# DressingEth.net
KiCad netlist of a schematic drawn in EasyEDA Pro
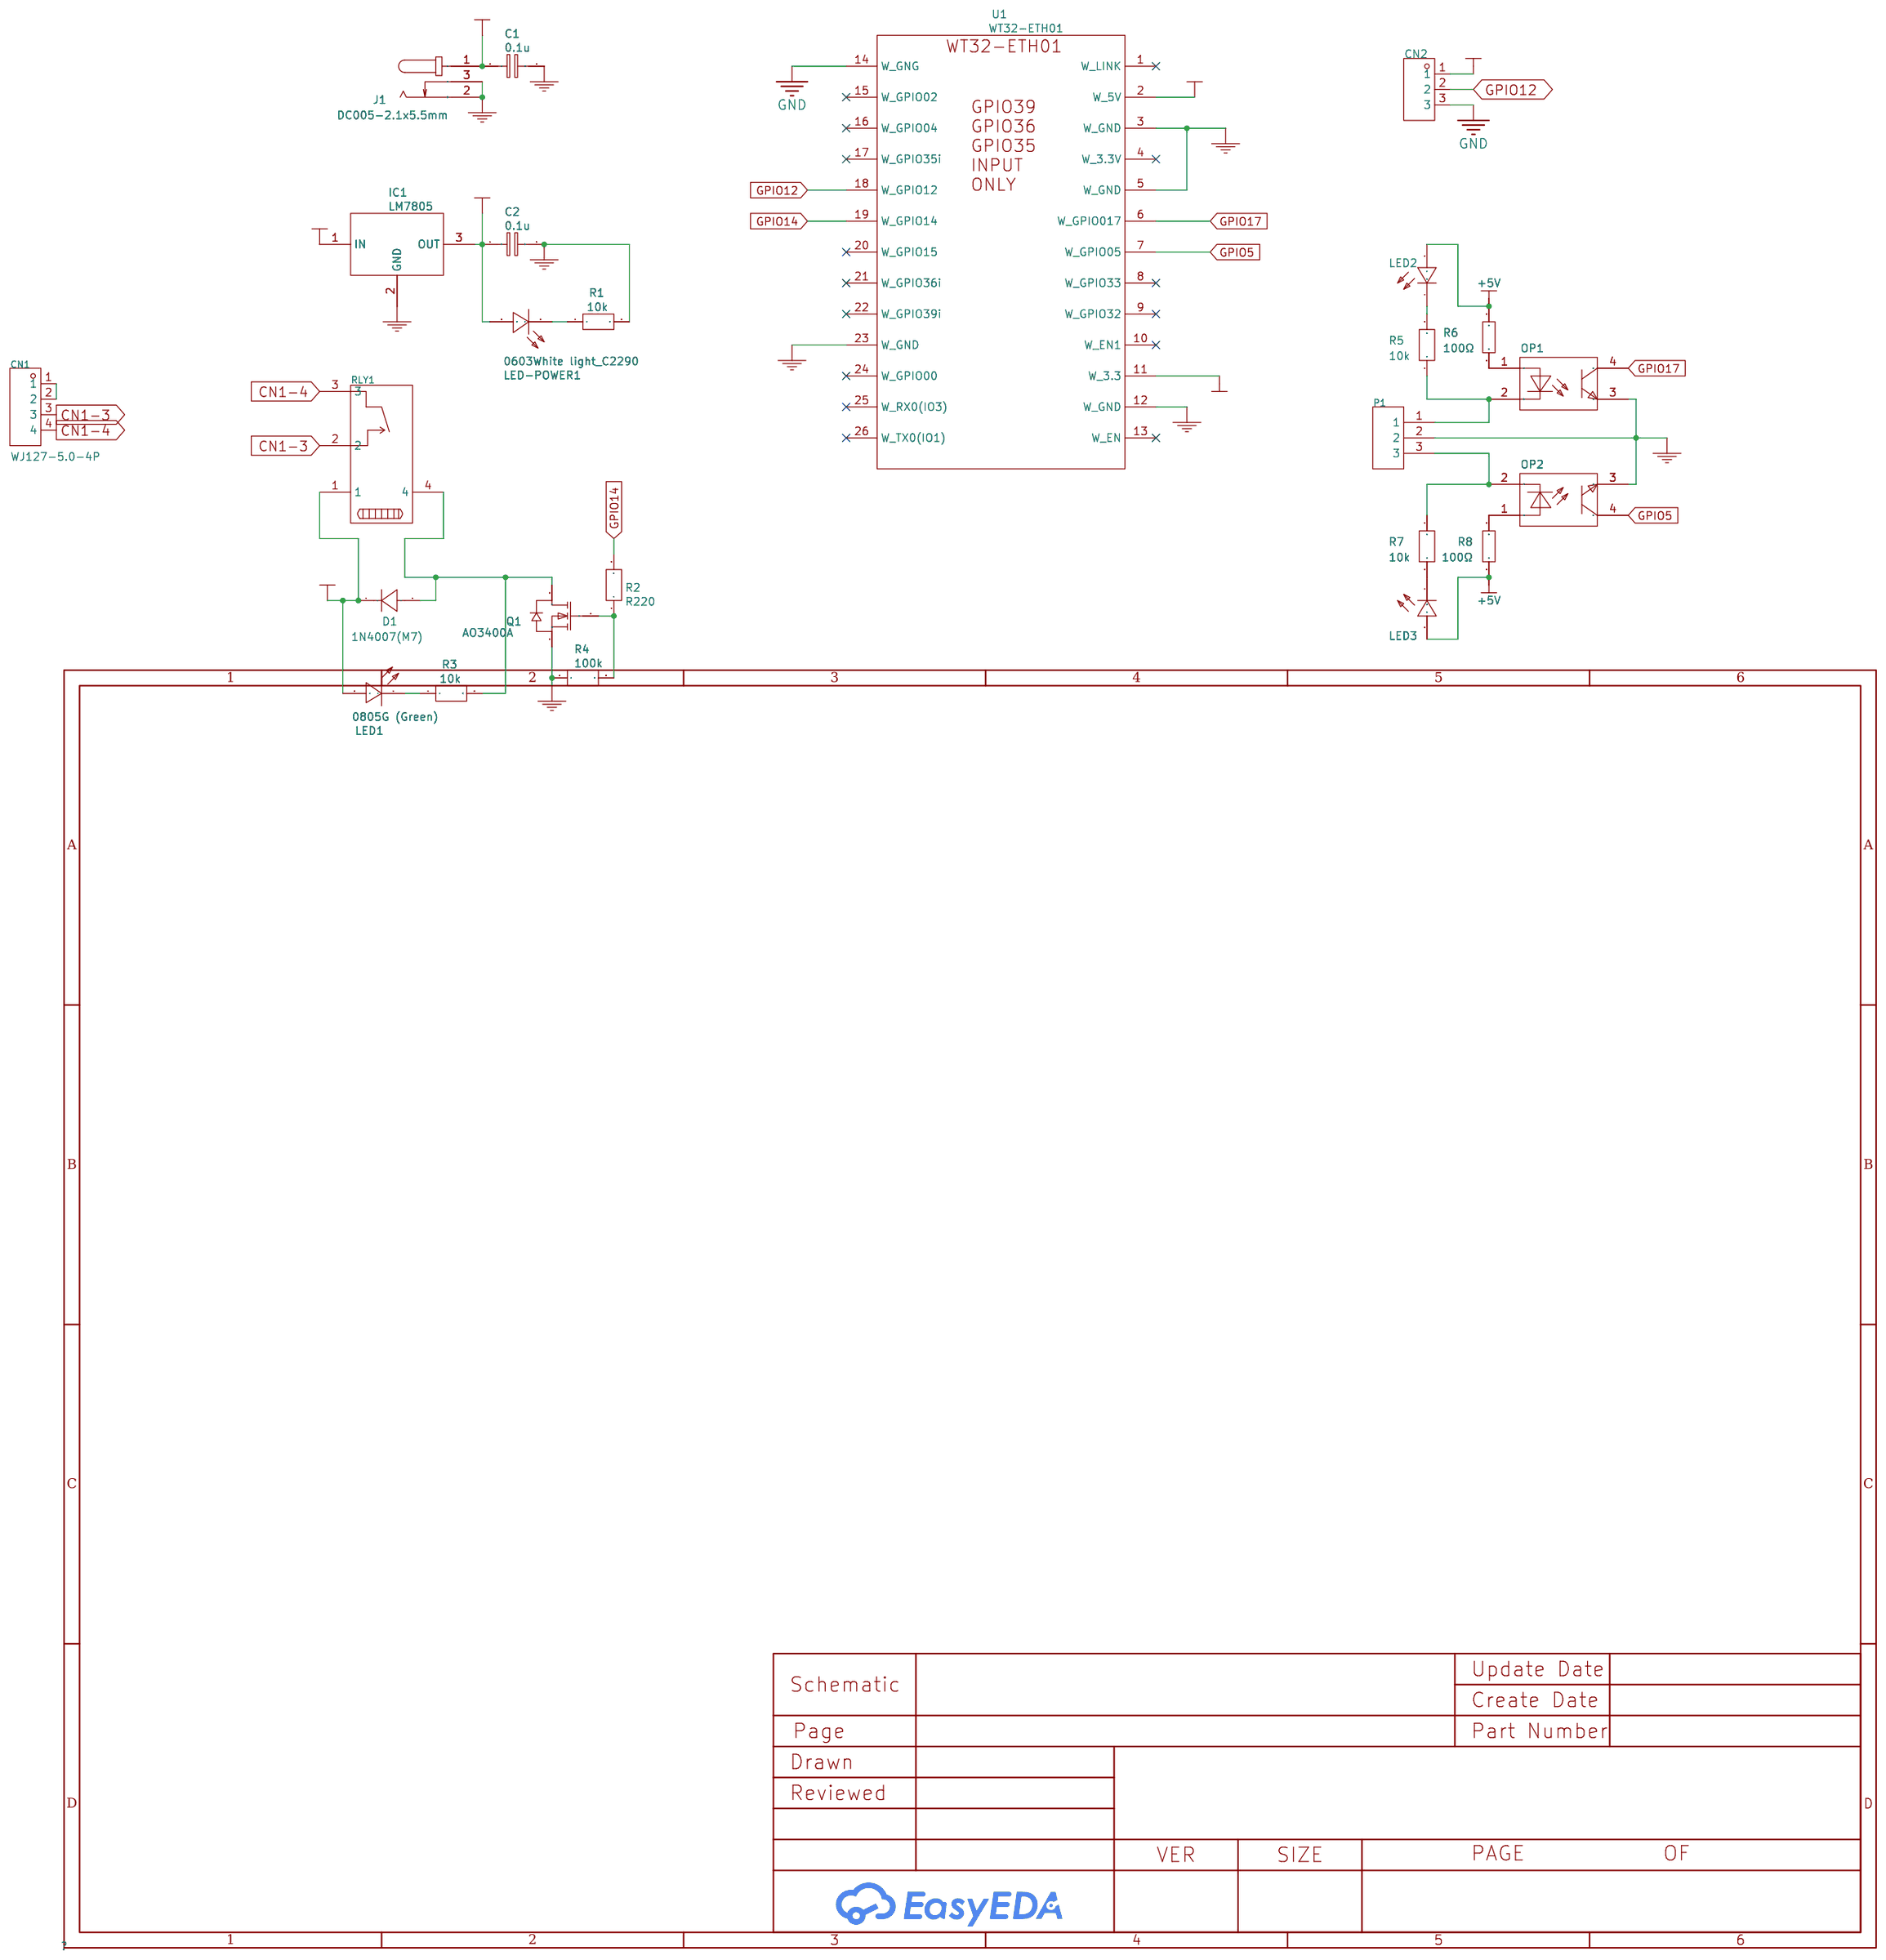
[diagram p0: schematic sheet]

(export (version "E")
  (design (tool "Eeschema 10.0.6"))
  (components
    (comp (ref "C1")
      (value "0.1u")
      (footprint "easyedapro:C0603")
      (fields
        (field (name "Manufacturer Part") "CL05B104KO5NNNC")
        (field (name "Manufacturer") "SAMSUNG(三星)")
      )
      (libsource (lib "easyedapro") (part "0.1u"))
    )
    (comp (ref "C2")
      (value "0.1u")
      (footprint "easyedapro:C0603")
      (fields
        (field (name "Manufacturer Part") "CL05B104KO5NNNC")
        (field (name "Manufacturer") "SAMSUNG(三星)")
      )
      (libsource (lib "easyedapro") (part "0.1u"))
    )
    (comp (ref "CN1")
      (value "WJ127-5.0-4P")
      (footprint "easyedapro:CONN-TH_4P-P5.00_WJ127-5.0-4P")
      (fields (field (name "Manufacturer") "KANGNEX(康奈克斯电气)"))
      (libsource (lib "easyedapro") (part "WJ127-5.0-4P"))
    )
    (comp (ref "CN2")
      (value "XH2.54-3A")
      (footprint "easyedapro:CONN-TH_3P-P2.50_HCTL_XH-3A-L")
      (libsource (lib "easyedapro") (part "XH2.54-3A"))
    )
    (comp (ref "D1")
      (value "1N4007(M7)")
      (footprint "easyedapro:SMA_L4.3-W2.7-LS5.1-RD")
      (fields (field (name "Manufacturer") "UMW(友台半导体)"))
      (libsource (lib "easyedapro") (part "1N4007(M7)"))
    )
    (comp (ref "IC1")
      (value "LM7805")
      (footprint "easyedapro:LM7805")
      (libsource (lib "easyedapro") (part "LM7805"))
    )
    (comp (ref "J1")
      (value "DC005-2.1x5.5mm")
      (footprint "easyedapro:DC-IN-TH_POWER-JACK")
      (fields (field (name "Manufacturer Part") "POWER-JACK") (field (name "Manufacturer") "索峰"))
      (libsource (lib "easyedapro") (part "DC005-2.1x5.5mm"))
    )
    (comp (ref "LED-POWER1")
      (value "0603White light_C2290")
      (footprint "easyedapro:LED0603-R-RD_WHITE")
      (fields (field (name "Manufacturer Part") "KT-0603W") (field (name "Manufacturer") "KENTO"))
      (libsource (lib "easyedapro") (part "0603White light_C2290"))
    )
    (comp (ref "LED1")
      (value "0805G (Green)")
      (footprint "easyedapro:LED0805-RD_GREEN")
      (fields (field (name "Manufacturer") "KENTO"))
      (libsource (lib "easyedapro") (part "0805G (Green)"))
    )
    (comp (ref "LED2")
      (value "19-213/Y2C-CQ2R2L/3T(CY)")
      (footprint "easyedapro:LED0603-RD-YELLOW")
      (fields (field (name "Manufacturer") "EVERLIGHT(亿光)"))
      (libsource (lib "easyedapro") (part "19-213/Y2C-CQ2R2L/3T(CY)"))
    )
    (comp (ref "LED3")
      (value "19-213/Y2C-CQ2R2L/3T(CY)")
      (footprint "easyedapro:LED0603-RD-YELLOW")
      (fields (field (name "Manufacturer") "EVERLIGHT(亿光)"))
      (libsource (lib "easyedapro") (part "19-213/Y2C-CQ2R2L/3T(CY)"))
    )
    (comp (ref "OP1")
      (value "EL817S1(C)(TU)-F")
      (footprint "easyedapro:OPTO-SMD-4_L4.6-W6.5-P2.54-LS10.3-TL")
      (fields (field (name "Manufacturer") "EVERLIGHT(亿光)"))
      (libsource (lib "easyedapro") (part "EL817S1(C)(TU)-F"))
    )
    (comp (ref "OP2")
      (value "EL817S1(C)(TU)-F")
      (footprint "easyedapro:OPTO-SMD-4_L4.6-W6.5-P2.54-LS10.3-TL")
      (fields (field (name "Manufacturer") "EVERLIGHT(亿光)"))
      (libsource (lib "easyedapro") (part "EL817S1(C)(TU)-F"))
    )
    (comp (ref "P1")
      (value "WJ127-5.0-3P")
      (footprint "easyedapro:CONN-TH_3P-P5.00_WJ127-5.0-3P")
      (fields (field (name "Manufacturer") "KANGNEX(康奈克斯电气)"))
      (libsource (lib "easyedapro") (part "WJ127-5.0-3P"))
    )
    (comp (ref "Q1")
      (value "AO3400A")
      (footprint "easyedapro:SOT-23-3_L2.9-W1.6-P1.90-LS2.8-BR")
      (fields (field (name "Manufacturer") "AOS"))
      (libsource (lib "easyedapro") (part "AO3400A"))
    )
    (comp (ref "R1")
      (value "10k")
      (footprint "easyedapro:R0603")
      (fields
        (field (name "Manufacturer Part") "0603WAF1002T5E")
        (field (name "Manufacturer") "UNI-ROYAL(厚声)")
      )
      (libsource (lib "easyedapro") (part "10k"))
    )
    (comp (ref "R2")
      (value "R220")
      (footprint "easyedapro:R0603")
      (fields
        (field (name "Manufacturer Part") "0603WAF2200T5E")
        (field (name "Manufacturer") "UNI-ROYAL(厚声)")
      )
      (libsource (lib "easyedapro") (part "R220"))
    )
    (comp (ref "R3")
      (value "10k")
      (footprint "easyedapro:R0603")
      (fields
        (field (name "Manufacturer Part") "0603WAF1002T5E")
        (field (name "Manufacturer") "UNI-ROYAL(厚声)")
      )
      (libsource (lib "easyedapro") (part "10k"))
    )
    (comp (ref "R4")
      (value "100k")
      (footprint "easyedapro:R0603")
      (fields
        (field (name "Manufacturer Part") "0603WAF1003T5E")
        (field (name "Manufacturer") "UNI-ROYAL(厚声)")
      )
      (libsource (lib "easyedapro") (part "100k"))
    )
    (comp (ref "R5")
      (value "10k")
      (footprint "easyedapro:R0603")
      (fields
        (field (name "Manufacturer Part") "0603WAF1002T5E")
        (field (name "Manufacturer") "UNI-ROYAL(厚声)")
      )
      (libsource (lib "easyedapro") (part "10k"))
    )
    (comp (ref "R6")
      (value "100Ω")
      (footprint "easyedapro:R0805")
      (fields
        (field (name "Manufacturer Part") "0805W8F1000T5E")
        (field (name "Manufacturer") "UNI-ROYAL(厚声)")
      )
      (libsource (lib "easyedapro") (part "0805W8F1000T5E"))
    )
    (comp (ref "R7")
      (value "10k")
      (footprint "easyedapro:R0603")
      (fields
        (field (name "Manufacturer Part") "0603WAF1002T5E")
        (field (name "Manufacturer") "UNI-ROYAL(厚声)")
      )
      (libsource (lib "easyedapro") (part "10k"))
    )
    (comp (ref "R8")
      (value "100Ω")
      (footprint "easyedapro:R0805")
      (fields
        (field (name "Manufacturer Part") "0805W8F1000T5E")
        (field (name "Manufacturer") "UNI-ROYAL(厚声)")
      )
      (libsource (lib "easyedapro") (part "0805W8F1000T5E"))
    )
    (comp (ref "RLY1")
      (value "G5NB-1A-E-DC5V")
      (footprint "easyedapro:RELAY-TH_G5NB-1A-E-DCXX")
      (fields (field (name "Manufacturer") "OMRON(欧姆龙)"))
      (libsource (lib "easyedapro") (part "G5NB-1A-E-DC5V"))
    )
    (comp (ref "U1")
      (value "WT32-ETH01")
      (footprint "easyedapro:WT32-ETH01-M")
      (fields (field (name "Manufacturer") "Wireless-Tag"))
      (libsource (lib "easyedapro") (part "WT32-ETH01"))
    )
  )
  (nets
    (net (code "1") (name "+3.3V") (class "Default")
      (node (ref "CN2") (pin "1") (pinfunction "1_1") (pintype "unspecified"))
      (node (ref "U1") (pin "11") (pinfunction "W_3.3_11") (pintype "unspecified"))
    )
    (net (code "2") (name "+5V") (class "Default")
      (node (ref "C2") (pin "1") (pinfunction "1_1") (pintype "unspecified"))
      (node (ref "D1") (pin "1") (pinfunction "K_1") (pintype "unspecified"))
      (node (ref "IC1") (pin "3") (pinfunction "OUT_3") (pintype "unspecified"))
      (node (ref "LED-POWER1") (pin "1") (pinfunction "A_1") (pintype "unspecified"))
      (node (ref "LED1") (pin "2") (pinfunction "A_2") (pintype "unspecified"))
      (node (ref "LED2") (pin "2") (pinfunction "A_2") (pintype "input"))
      (node (ref "LED3") (pin "2") (pinfunction "A_2") (pintype "input"))
      (node (ref "R6") (pin "1") (pinfunction "1_1") (pintype "input"))
      (node (ref "R8") (pin "1") (pinfunction "1_1") (pintype "input"))
      (node (ref "RLY1") (pin "1") (pinfunction "1_1") (pintype "input"))
      (node (ref "U1") (pin "2") (pinfunction "W_5V_2") (pintype "unspecified"))
    )
    (net (code "3") (name "CN1-3") (class "Default")
      (node (ref "CN1") (pin "3") (pinfunction "3_3") (pintype "input"))
      (node (ref "RLY1") (pin "2") (pinfunction "2_2") (pintype "input"))
    )
    (net (code "4") (name "CN1-4") (class "Default")
      (node (ref "CN1") (pin "4") (pinfunction "4_4") (pintype "input"))
      (node (ref "RLY1") (pin "3") (pinfunction "3_3") (pintype "input"))
    )
    (net (code "5") (name "GND") (class "Default")
      (node (ref "C1") (pin "2") (pinfunction "2_2") (pintype "unspecified"))
      (node (ref "C2") (pin "2") (pinfunction "2_2") (pintype "unspecified"))
      (node (ref "CN2") (pin "3") (pinfunction "3_3") (pintype "unspecified"))
      (node (ref "IC1") (pin "2") (pinfunction "GND_2") (pintype "unspecified"))
      (node (ref "J1") (pin "2") (pinfunction "GND_2") (pintype "unspecified"))
      (node (ref "J1") (pin "3") (pinfunction "3_3") (pintype "unspecified"))
      (node (ref "OP1") (pin "3") (pinfunction "EM_3") (pintype "unspecified"))
      (node (ref "OP2") (pin "3") (pinfunction "EM_3") (pintype "unspecified"))
      (node (ref "P1") (pin "2") (pinfunction "2_2") (pintype "input"))
      (node (ref "Q1") (pin "2") (pinfunction "S_2") (pintype "unspecified"))
      (node (ref "R1") (pin "2") (pinfunction "2_2") (pintype "unspecified"))
      (node (ref "R4") (pin "1") (pinfunction "1_1") (pintype "unspecified"))
      (node (ref "U1") (pin "12") (pinfunction "W_GND_12") (pintype "unspecified"))
      (node (ref "U1") (pin "14") (pinfunction "W_GNG_14") (pintype "unspecified"))
      (node (ref "U1") (pin "23") (pinfunction "W_GND_23") (pintype "unspecified"))
      (node (ref "U1") (pin "3") (pinfunction "W_GND_3") (pintype "unspecified"))
      (node (ref "U1") (pin "5") (pinfunction "W_GND_5") (pintype "unspecified"))
    )
    (net (code "6") (name "GPIO5") (class "Default")
      (node (ref "OP2") (pin "4") (pinfunction "COL_4") (pintype "unspecified"))
      (node (ref "U1") (pin "7") (pinfunction "W_GPIO05_7") (pintype "unspecified"))
    )
    (net (code "7") (name "GPIO12") (class "Default")
      (node (ref "CN2") (pin "2") (pinfunction "2_2") (pintype "unspecified"))
      (node (ref "U1") (pin "18") (pinfunction "W_GPIO12_18") (pintype "unspecified"))
    )
    (net (code "8") (name "GPIO14") (class "Default")
      (node (ref "R2") (pin "2") (pinfunction "2_2") (pintype "unspecified"))
      (node (ref "U1") (pin "19") (pinfunction "W_GPIO14_19") (pintype "unspecified"))
    )
    (net (code "9") (name "GPIO17") (class "Default")
      (node (ref "OP1") (pin "4") (pinfunction "COL_4") (pintype "unspecified"))
      (node (ref "U1") (pin "6") (pinfunction "W_GPIO017_6") (pintype "unspecified"))
    )
    (net (code "10") (name "Net-(CN1-Pad1)") (class "Default")
      (node (ref "CN1") (pin "1") (pinfunction "1_1") (pintype "input"))
      (node (ref "CN1") (pin "2") (pinfunction "2_2") (pintype "input"))
    )
    (net (code "11") (name "Net-(D1-A)") (class "Default")
      (node (ref "D1") (pin "2") (pinfunction "A_2") (pintype "unspecified"))
      (node (ref "Q1") (pin "3") (pinfunction "D_3") (pintype "unspecified"))
      (node (ref "R3") (pin "2") (pinfunction "2_2") (pintype "unspecified"))
      (node (ref "RLY1") (pin "4") (pinfunction "4_4") (pintype "input"))
    )
    (net (code "12") (name "Net-(LED-POWER1-K)") (class "Default")
      (node (ref "LED-POWER1") (pin "2") (pinfunction "K_2") (pintype "unspecified"))
      (node (ref "R1") (pin "1") (pinfunction "1_1") (pintype "unspecified"))
    )
    (net (code "13") (name "Net-(LED1-K)") (class "Default")
      (node (ref "LED1") (pin "1") (pinfunction "K_1") (pintype "unspecified"))
      (node (ref "R3") (pin "1") (pinfunction "1_1") (pintype "unspecified"))
    )
    (net (code "14") (name "Net-(LED2-C)") (class "Default")
      (node (ref "LED2") (pin "1") (pinfunction "C_1") (pintype "input"))
      (node (ref "R5") (pin "2") (pinfunction "2_2") (pintype "unspecified"))
    )
    (net (code "15") (name "Net-(LED3-C)") (class "Default")
      (node (ref "LED3") (pin "1") (pinfunction "C_1") (pintype "input"))
      (node (ref "R7") (pin "2") (pinfunction "2_2") (pintype "unspecified"))
    )
    (net (code "16") (name "Net-(OP1-AN)") (class "Default")
      (node (ref "OP1") (pin "1") (pinfunction "AN_1") (pintype "unspecified"))
      (node (ref "R6") (pin "2") (pinfunction "2_2") (pintype "input"))
    )
    (net (code "17") (name "Net-(OP1-CAT)") (class "Default")
      (node (ref "OP1") (pin "2") (pinfunction "CAT_2") (pintype "unspecified"))
      (node (ref "P1") (pin "1") (pinfunction "1_1") (pintype "input"))
      (node (ref "R5") (pin "1") (pinfunction "1_1") (pintype "unspecified"))
    )
    (net (code "18") (name "Net-(OP2-AN)") (class "Default")
      (node (ref "OP2") (pin "1") (pinfunction "AN_1") (pintype "unspecified"))
      (node (ref "R8") (pin "2") (pinfunction "2_2") (pintype "input"))
    )
    (net (code "19") (name "Net-(OP2-CAT)") (class "Default")
      (node (ref "OP2") (pin "2") (pinfunction "CAT_2") (pintype "unspecified"))
      (node (ref "P1") (pin "3") (pinfunction "3_3") (pintype "input"))
      (node (ref "R7") (pin "1") (pinfunction "1_1") (pintype "unspecified"))
    )
    (net (code "20") (name "Net-(Q1-G)") (class "Default")
      (node (ref "Q1") (pin "1") (pinfunction "G_1") (pintype "unspecified"))
      (node (ref "R2") (pin "1") (pinfunction "1_1") (pintype "unspecified"))
      (node (ref "R4") (pin "2") (pinfunction "2_2") (pintype "unspecified"))
    )
    (net (code "21") (name "VCC") (class "Default")
      (node (ref "C1") (pin "1") (pinfunction "1_1") (pintype "unspecified"))
      (node (ref "IC1") (pin "1") (pinfunction "IN_1") (pintype "unspecified"))
      (node (ref "J1") (pin "1") (pinfunction "VCC_1") (pintype "unspecified"))
    )
    (net (code "22") (name "unconnected-(U1-W_3.3V-Pad4)") (class "Default")
      (node (ref "U1") (pin "4") (pinfunction "W_3.3V_4") (pintype "unspecified+no_connect"))
    )
    (net (code "23") (name "unconnected-(U1-W_EN-Pad13)") (class "Default")
      (node (ref "U1") (pin "13") (pinfunction "W_EN_13") (pintype "unspecified+no_connect"))
    )
    (net (code "24") (name "unconnected-(U1-W_EN1-Pad10)") (class "Default")
      (node (ref "U1") (pin "10") (pinfunction "W_EN1_10") (pintype "unspecified+no_connect"))
    )
    (net (code "25") (name "unconnected-(U1-W_GPIO00-Pad24)") (class "Default")
      (node (ref "U1") (pin "24") (pinfunction "W_GPIO00_24") (pintype "unspecified+no_connect"))
    )
    (net (code "26") (name "unconnected-(U1-W_GPIO02-Pad15)") (class "Default")
      (node (ref "U1") (pin "15") (pinfunction "W_GPIO02_15") (pintype "unspecified+no_connect"))
    )
    (net (code "27") (name "unconnected-(U1-W_GPIO04-Pad16)") (class "Default")
      (node (ref "U1") (pin "16") (pinfunction "W_GPIO04_16") (pintype "unspecified+no_connect"))
    )
    (net (code "28") (name "unconnected-(U1-W_GPIO15-Pad20)") (class "Default")
      (node (ref "U1") (pin "20") (pinfunction "W_GPIO15_20") (pintype "unspecified+no_connect"))
    )
    (net (code "29") (name "unconnected-(U1-W_GPIO32-Pad9)") (class "Default")
      (node (ref "U1") (pin "9") (pinfunction "W_GPIO32_9") (pintype "unspecified+no_connect"))
    )
    (net (code "30") (name "unconnected-(U1-W_GPIO33-Pad8)") (class "Default")
      (node (ref "U1") (pin "8") (pinfunction "W_GPIO33_8") (pintype "unspecified+no_connect"))
    )
    (net (code "31") (name "unconnected-(U1-W_GPIO35i-Pad17)") (class "Default")
      (node (ref "U1") (pin "17") (pinfunction "W_GPIO35i_17") (pintype "unspecified+no_connect"))
    )
    (net (code "32") (name "unconnected-(U1-W_GPIO36i-Pad21)") (class "Default")
      (node (ref "U1") (pin "21") (pinfunction "W_GPIO36i_21") (pintype "unspecified+no_connect"))
    )
    (net (code "33") (name "unconnected-(U1-W_GPIO39i-Pad22)") (class "Default")
      (node (ref "U1") (pin "22") (pinfunction "W_GPIO39i_22") (pintype "unspecified+no_connect"))
    )
    (net (code "34") (name "unconnected-(U1-W_LINK-Pad1)") (class "Default")
      (node (ref "U1") (pin "1") (pinfunction "W_LINK_1") (pintype "unspecified+no_connect"))
    )
    (net (code "35") (name "unconnected-(U1-W_RX0(IO3)-Pad25)") (class "Default")
      (node (ref "U1") (pin "25") (pinfunction "W_RX0(IO3)_25") (pintype "unspecified+no_connect"))
    )
    (net (code "36") (name "unconnected-(U1-W_TX0(IO1)-Pad26)") (class "Default")
      (node (ref "U1") (pin "26") (pinfunction "W_TX0(IO1)_26") (pintype "unspecified+no_connect"))
    )
  )
)
